# TEST_DCDC.net
KiCad netlist of a schematic drawn in EAGLE
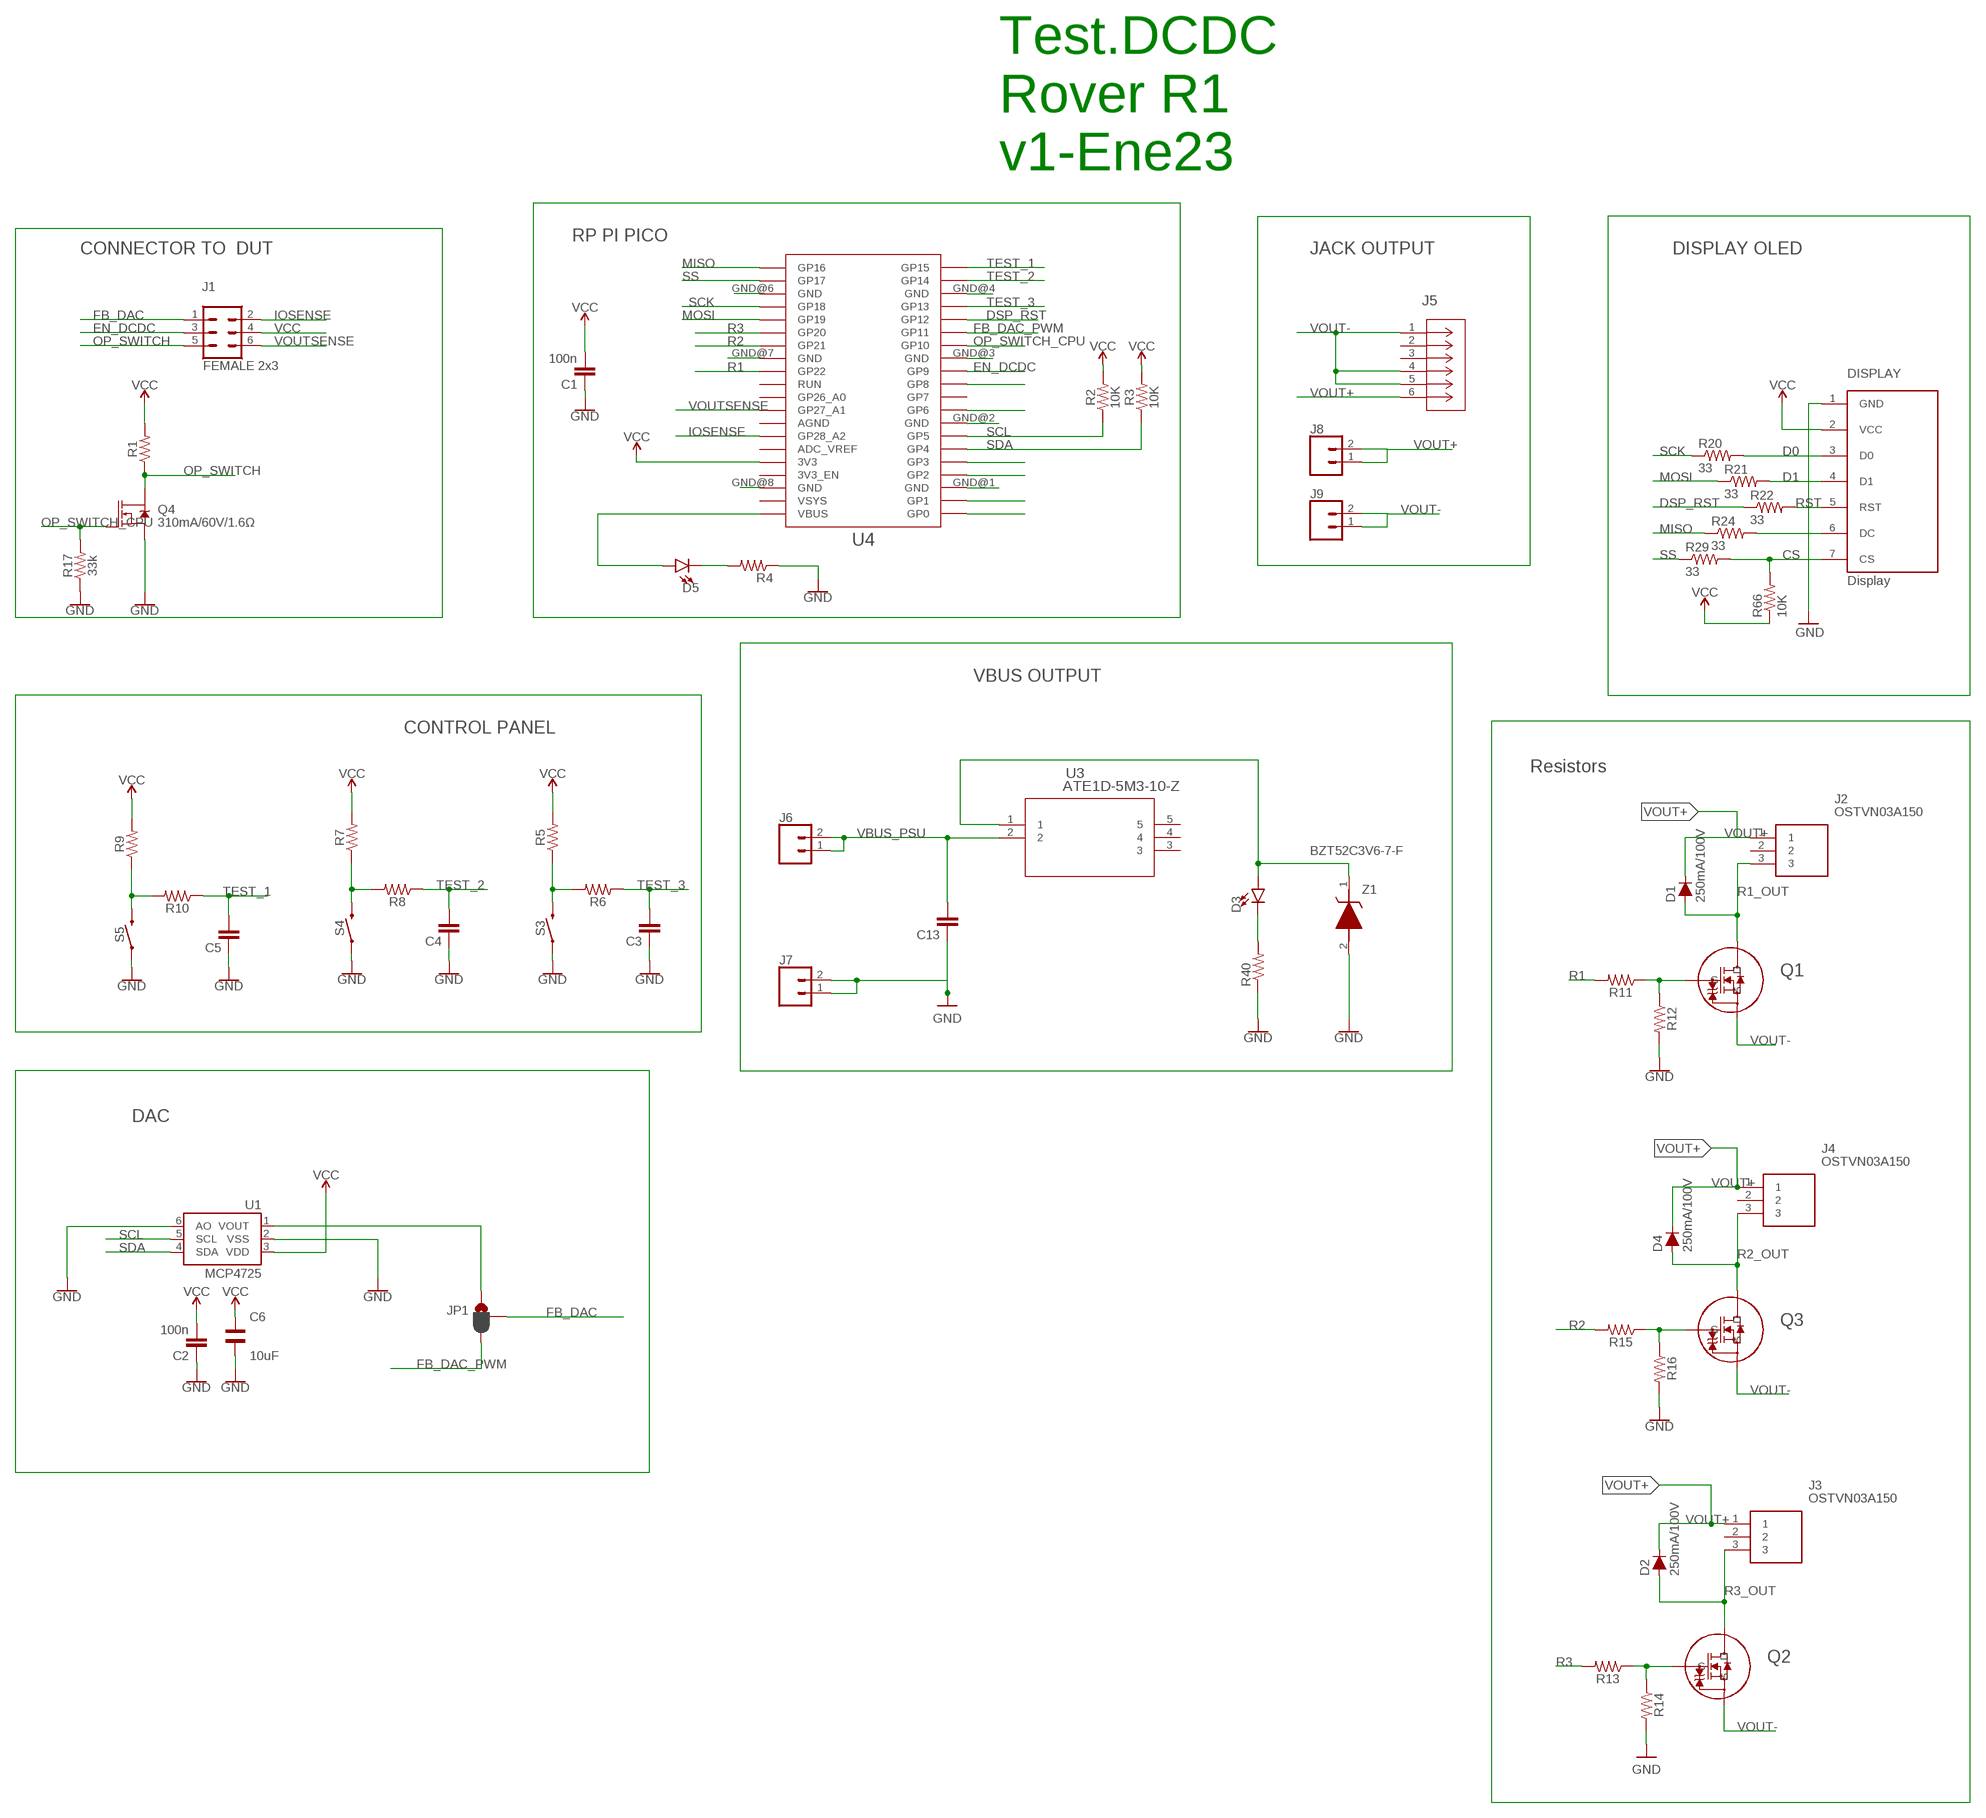
[diagram p0: schematic, sheet 1]

(export (version "E")
  (design (tool "Eeschema 10.0.6"))
  (components
    (comp (ref "C1")
      (value "100n")
      (footprint "eagle-import:C0805")
      (libsource (lib "eagle-import") (part "C-EUC0805"))
    )
    (comp (ref "C2")
      (value "100n")
      (footprint "eagle-import:C0805")
      (libsource (lib "eagle-import") (part "C-EUC0805"))
    )
    (comp (ref "C3")
      (value "C-EUC0805")
      (footprint "eagle-import:C0805")
      (libsource (lib "eagle-import") (part "C-EUC0805"))
    )
    (comp (ref "C4")
      (value "C-EUC0805")
      (footprint "eagle-import:C0805")
      (libsource (lib "eagle-import") (part "C-EUC0805"))
    )
    (comp (ref "C5")
      (value "C-EUC0805")
      (footprint "eagle-import:C0805")
      (libsource (lib "eagle-import") (part "C-EUC0805"))
    )
    (comp (ref "C6")
      (value "10uF")
      (footprint "eagle-import:WCAP-CSGP_1206")
      (libsource (lib "eagle-import") (part "WCAP-CSGP_1206_885012008001"))
    )
    (comp (ref "C13")
      (value "C-EUC0805")
      (footprint "eagle-import:C0805")
      (libsource (lib "eagle-import") (part "C-EUC0805"))
    )
    (comp (ref "D1")
      (value "250mA/100V")
      (footprint "eagle-import:SOD-323")
      (libsource (lib "eagle-import") (part "DIODE-BAS16J"))
    )
    (comp (ref "D2")
      (value "250mA/100V")
      (footprint "eagle-import:SOD-323")
      (libsource (lib "eagle-import") (part "DIODE-BAS16J"))
    )
    (comp (ref "D3")
      (value "LED3MM")
      (footprint "eagle-import:LED_3MM")
      (libsource (lib "eagle-import") (part "LED3MM"))
    )
    (comp (ref "D4")
      (value "250mA/100V")
      (footprint "eagle-import:SOD-323")
      (libsource (lib "eagle-import") (part "DIODE-BAS16J"))
    )
    (comp (ref "D5")
      (value "LED3MM")
      (footprint "eagle-import:LED_3MM")
      (libsource (lib "eagle-import") (part "LED3MM"))
    )
    (comp (ref "DISPLAY")
      (value "Display")
      (footprint "eagle-import:OLED_LCD")
      (libsource (lib "eagle-import") (part "OLED_LCD"))
    )
    (comp (ref "J1")
      (value "FEMALE 2x3")
      (footprint "eagle-import:2X3")
      (libsource (lib "eagle-import") (part "CONN_03X2FEMALE"))
    )
    (comp (ref "J2")
      (value "OSTVN03A150")
      (footprint "eagle-import:OSTVN03A150")
      (libsource (lib "eagle-import") (part "OSTVN03A150"))
    )
    (comp (ref "J3")
      (value "OSTVN03A150")
      (footprint "eagle-import:OSTVN03A150")
      (libsource (lib "eagle-import") (part "OSTVN03A150"))
    )
    (comp (ref "J4")
      (value "OSTVN03A150")
      (footprint "eagle-import:OSTVN03A150")
      (libsource (lib "eagle-import") (part "OSTVN03A150"))
    )
    (comp (ref "J5")
      (value "ACJS-MHDR")
      (footprint "eagle-import:CONN_MHDR_AMP")
      (fields (field (name "COPYRIGHT") "Copyright (C) 2018 Accelerated Designs. All rights reserved"))
      (libsource (lib "eagle-import") (part "ACJS-MHDR"))
    )
    (comp (ref "J6")
      (value "CONN_02")
      (footprint "eagle-import:1X02")
      (libsource (lib "eagle-import") (part "CONN_02"))
    )
    (comp (ref "J7")
      (value "CONN_02")
      (footprint "eagle-import:1X02")
      (libsource (lib "eagle-import") (part "CONN_02"))
    )
    (comp (ref "J8")
      (value "CONN_02")
      (footprint "eagle-import:1X02")
      (libsource (lib "eagle-import") (part "CONN_02"))
    )
    (comp (ref "J9")
      (value "CONN_02")
      (footprint "eagle-import:1X02")
      (libsource (lib "eagle-import") (part "CONN_02"))
    )
    (comp (ref "JP1")
      (value "JUMPER-SMT_3_1-NC_PASTE_SILK")
      (footprint "eagle-import:SMT-JUMPER_3_1-NC_PASTE_SILK")
      (libsource (lib "eagle-import") (part "JUMPER-SMT_3_1-NC_PASTE_SILK"))
    )
    (comp (ref "Q1")
      (value "PJA3416AE_R1_00001")
      (footprint "eagle-import:SOT23_PJA3416_PNJ")
      (fields (field (name "COPYRIGHT") "Copyright (C) 2022 Ultra Librarian. All rights reserved."))
      (libsource (lib "eagle-import") (part "PJA3416AE_R1_00001"))
    )
    (comp (ref "Q2")
      (value "PJA3416AE_R1_00001")
      (footprint "eagle-import:SOT23_PJA3416_PNJ")
      (fields (field (name "COPYRIGHT") "Copyright (C) 2022 Ultra Librarian. All rights reserved."))
      (libsource (lib "eagle-import") (part "PJA3416AE_R1_00001"))
    )
    (comp (ref "Q3")
      (value "PJA3416AE_R1_00001")
      (footprint "eagle-import:SOT23_PJA3416_PNJ")
      (fields (field (name "COPYRIGHT") "Copyright (C) 2022 Ultra Librarian. All rights reserved."))
      (libsource (lib "eagle-import") (part "PJA3416AE_R1_00001"))
    )
    (comp (ref "Q4")
      (value "310mA/60V/1.6Ω")
      (footprint "eagle-import:SOT323")
      (libsource (lib "eagle-import") (part "MOSFET-NCH-2N7002PW"))
    )
    (comp (ref "R1")
      (value "RESISTOR0805")
      (footprint "eagle-import:0805")
      (libsource (lib "eagle-import") (part "RESISTOR0805"))
    )
    (comp (ref "R2")
      (value "10K")
      (footprint "eagle-import:0805")
      (libsource (lib "eagle-import") (part "RESISTOR0805"))
    )
    (comp (ref "R3")
      (value "10K")
      (footprint "eagle-import:0805")
      (libsource (lib "eagle-import") (part "RESISTOR0805"))
    )
    (comp (ref "R4")
      (value "10K")
      (footprint "eagle-import:0805")
      (libsource (lib "eagle-import") (part "RESISTOR0805-RES"))
    )
    (comp (ref "R5")
      (value "RESISTOR0805")
      (footprint "eagle-import:0805")
      (libsource (lib "eagle-import") (part "RESISTOR0805"))
    )
    (comp (ref "R6")
      (value "RESISTOR0805")
      (footprint "eagle-import:0805")
      (libsource (lib "eagle-import") (part "RESISTOR0805"))
    )
    (comp (ref "R7")
      (value "RESISTOR0805")
      (footprint "eagle-import:0805")
      (libsource (lib "eagle-import") (part "RESISTOR0805"))
    )
    (comp (ref "R8")
      (value "RESISTOR0805")
      (footprint "eagle-import:0805")
      (libsource (lib "eagle-import") (part "RESISTOR0805"))
    )
    (comp (ref "R9")
      (value "RESISTOR0805")
      (footprint "eagle-import:0805")
      (libsource (lib "eagle-import") (part "RESISTOR0805"))
    )
    (comp (ref "R10")
      (value "RESISTOR0805")
      (footprint "eagle-import:0805")
      (libsource (lib "eagle-import") (part "RESISTOR0805"))
    )
    (comp (ref "R11")
      (value "RESISTOR0805")
      (footprint "eagle-import:0805")
      (libsource (lib "eagle-import") (part "RESISTOR0805"))
    )
    (comp (ref "R12")
      (value "RESISTOR0805")
      (footprint "eagle-import:0805")
      (libsource (lib "eagle-import") (part "RESISTOR0805"))
    )
    (comp (ref "R13")
      (value "RESISTOR0805")
      (footprint "eagle-import:0805")
      (libsource (lib "eagle-import") (part "RESISTOR0805"))
    )
    (comp (ref "R14")
      (value "RESISTOR0805")
      (footprint "eagle-import:0805")
      (libsource (lib "eagle-import") (part "RESISTOR0805"))
    )
    (comp (ref "R15")
      (value "RESISTOR0805")
      (footprint "eagle-import:0805")
      (libsource (lib "eagle-import") (part "RESISTOR0805"))
    )
    (comp (ref "R16")
      (value "RESISTOR0805")
      (footprint "eagle-import:0805")
      (libsource (lib "eagle-import") (part "RESISTOR0805"))
    )
    (comp (ref "R17")
      (value "33k")
      (footprint "eagle-import:0805")
      (libsource (lib "eagle-import") (part "RESISTOR0805"))
    )
    (comp (ref "R20")
      (value "33")
      (footprint "eagle-import:0805")
      (libsource (lib "eagle-import") (part "RESISTOR0805-RES"))
    )
    (comp (ref "R21")
      (value "33")
      (footprint "eagle-import:0805")
      (libsource (lib "eagle-import") (part "RESISTOR0805-RES"))
    )
    (comp (ref "R22")
      (value "33")
      (footprint "eagle-import:0805")
      (libsource (lib "eagle-import") (part "RESISTOR0805-RES"))
    )
    (comp (ref "R24")
      (value "33")
      (footprint "eagle-import:0805")
      (libsource (lib "eagle-import") (part "RESISTOR0805-RES"))
    )
    (comp (ref "R29")
      (value "33")
      (footprint "eagle-import:0805")
      (libsource (lib "eagle-import") (part "RESISTOR0805-RES"))
    )
    (comp (ref "R40")
      (value "10K")
      (footprint "eagle-import:0805")
      (libsource (lib "eagle-import") (part "RESISTOR0805-RES"))
    )
    (comp (ref "R66")
      (value "10K")
      (footprint "eagle-import:0805")
      (libsource (lib "eagle-import") (part "RESISTOR0805-RES"))
    )
    (comp (ref "S3")
      (value "MOMENTARY-SWITCH-SPST-SMD-5.2MM")
      (footprint "eagle-import:TACTILE_SWITCH_SMD_5.2MM")
      (libsource (lib "eagle-import") (part "MOMENTARY-SWITCH-SPST-SMD-5.2MM"))
    )
    (comp (ref "S4")
      (value "MOMENTARY-SWITCH-SPST-SMD-5.2MM")
      (footprint "eagle-import:TACTILE_SWITCH_SMD_5.2MM")
      (libsource (lib "eagle-import") (part "MOMENTARY-SWITCH-SPST-SMD-5.2MM"))
    )
    (comp (ref "S5")
      (value "MOMENTARY-SWITCH-SPST-SMD-5.2MM")
      (footprint "eagle-import:TACTILE_SWITCH_SMD_5.2MM")
      (libsource (lib "eagle-import") (part "MOMENTARY-SWITCH-SPST-SMD-5.2MM"))
    )
    (comp (ref "U1")
      (value "MCP4725")
      (footprint "eagle-import:SOT23-6")
      (libsource (lib "eagle-import") (part "MCP4725SOT-23"))
    )
    (comp (ref "U3")
      (value "ATE1D-5M3-10-Z")
      (footprint "eagle-import:SPDT05_ATE1D_9P5X8_NDC")
      (fields (field (name "COPYRIGHT") "Copyright (C) 2022 Ultra Librarian. All rights reserved."))
      (libsource (lib "eagle-import") (part "ATE1D-5M3-10-Z"))
    )
    (comp (ref "U4")
      (value "RPI_PICO_IG-TH")
      (footprint "eagle-import:RPI_PICO_TH")
      (libsource (lib "eagle-import") (part "RPI_PICO_IG-TH"))
    )
    (comp (ref "Z1")
      (value "BZT52C3V6-7-F")
      (footprint "eagle-import:SOD3716X135N")
      (fields (field (name "MOUSER_PART_NUMBER") "621-BZT52C3V6-F"))
      (libsource (lib "eagle-import") (part "BZT52C3V6-7-F"))
    )
  )
  (nets
    (net (code "1") (name "/CS") (class "Default")
      (node (ref "DISPLAY") (pin "7") (pinfunction "CS_7") (pintype "bidirectional"))
      (node (ref "R29") (pin "2") (pinfunction "2_2") (pintype "passive"))
      (node (ref "R66") (pin "2") (pinfunction "2_2") (pintype "passive"))
    )
    (net (code "2") (name "/D0") (class "Default")
      (node (ref "DISPLAY") (pin "3") (pinfunction "D0_3") (pintype "bidirectional"))
      (node (ref "R20") (pin "2") (pinfunction "2_2") (pintype "passive"))
    )
    (net (code "3") (name "/D1") (class "Default")
      (node (ref "DISPLAY") (pin "4") (pinfunction "D1_4") (pintype "bidirectional"))
      (node (ref "R21") (pin "2") (pinfunction "2_2") (pintype "passive"))
    )
    (net (code "4") (name "/DSP_RST") (class "Default")
      (node (ref "R22") (pin "1") (pinfunction "1_1") (pintype "passive"))
      (node (ref "U4") (pin "GP12") (pinfunction "GP12_GP12") (pintype "bidirectional"))
    )
    (net (code "5") (name "/EN_DCDC") (class "Default")
      (node (ref "J1") (pin "3") (pinfunction "3_3") (pintype "bidirectional"))
      (node (ref "U4") (pin "GP9") (pinfunction "GP9_GP9") (pintype "bidirectional"))
    )
    (net (code "6") (name "/FB_DAC") (class "Default")
      (node (ref "J1") (pin "1") (pinfunction "1_1") (pintype "bidirectional"))
      (node (ref "JP1") (pin "2") (pinfunction "2_2") (pintype "passive"))
    )
    (net (code "7") (name "/FB_DAC_PWM") (class "Default")
      (node (ref "JP1") (pin "3") (pinfunction "3_3") (pintype "passive"))
      (node (ref "U4") (pin "GP11") (pinfunction "GP11_GP11") (pintype "bidirectional"))
    )
    (net (code "8") (name "/IOSENSE") (class "Default")
      (node (ref "J1") (pin "2") (pinfunction "2_2") (pintype "bidirectional"))
      (node (ref "U4") (pin "GP28_A2") (pinfunction "GP28_A2_GP28_A2") (pintype "bidirectional"))
    )
    (net (code "9") (name "/MISO") (class "Default")
      (node (ref "R24") (pin "1") (pinfunction "1_1") (pintype "passive"))
      (node (ref "U4") (pin "GP16") (pinfunction "GP16_GP16") (pintype "bidirectional"))
    )
    (net (code "10") (name "/MOSI") (class "Default")
      (node (ref "R21") (pin "1") (pinfunction "1_1") (pintype "passive"))
      (node (ref "U4") (pin "GP19") (pinfunction "GP19_GP19") (pintype "bidirectional"))
    )
    (net (code "11") (name "/OP_SWITCH") (class "Default")
      (node (ref "J1") (pin "5") (pinfunction "5_5") (pintype "bidirectional"))
      (node (ref "Q4") (pin "3") (pinfunction "D_3") (pintype "bidirectional"))
      (node (ref "R1") (pin "1") (pinfunction "1_1") (pintype "passive"))
    )
    (net (code "12") (name "/OP_SWITCH_CPU") (class "Default")
      (node (ref "Q4") (pin "1") (pinfunction "G_1") (pintype "bidirectional"))
      (node (ref "R17") (pin "2") (pinfunction "2_2") (pintype "passive"))
      (node (ref "U4") (pin "GP10") (pinfunction "GP10_GP10") (pintype "bidirectional"))
    )
    (net (code "13") (name "/R1") (class "Default")
      (node (ref "R11") (pin "2") (pinfunction "2_2") (pintype "passive"))
      (node (ref "U4") (pin "GP22") (pinfunction "GP22_GP22") (pintype "bidirectional"))
    )
    (net (code "14") (name "/R1_OUT") (class "Default")
      (node (ref "D1") (pin "A") (pinfunction "A_A") (pintype "passive"))
      (node (ref "J2") (pin "3") (pinfunction "3_3") (pintype "bidirectional"))
      (node (ref "Q1") (pin "3") (pinfunction "D_3") (pintype "passive"))
    )
    (net (code "15") (name "/R2") (class "Default")
      (node (ref "R15") (pin "2") (pinfunction "2_2") (pintype "passive"))
      (node (ref "U4") (pin "GP21") (pinfunction "GP21_GP21") (pintype "bidirectional"))
    )
    (net (code "16") (name "/R2_OUT") (class "Default")
      (node (ref "D4") (pin "A") (pinfunction "A_A") (pintype "passive"))
      (node (ref "J4") (pin "3") (pinfunction "3_3") (pintype "bidirectional"))
      (node (ref "Q3") (pin "3") (pinfunction "D_3") (pintype "passive"))
    )
    (net (code "17") (name "/R3") (class "Default")
      (node (ref "R13") (pin "2") (pinfunction "2_2") (pintype "passive"))
      (node (ref "U4") (pin "GP20") (pinfunction "GP20_GP20") (pintype "bidirectional"))
    )
    (net (code "18") (name "/R3_OUT") (class "Default")
      (node (ref "D2") (pin "A") (pinfunction "A_A") (pintype "passive"))
      (node (ref "J3") (pin "3") (pinfunction "3_3") (pintype "bidirectional"))
      (node (ref "Q2") (pin "3") (pinfunction "D_3") (pintype "passive"))
    )
    (net (code "19") (name "/RST") (class "Default")
      (node (ref "DISPLAY") (pin "5") (pinfunction "RST_5") (pintype "bidirectional"))
      (node (ref "R22") (pin "2") (pinfunction "2_2") (pintype "passive"))
    )
    (net (code "20") (name "/SCK") (class "Default")
      (node (ref "R20") (pin "1") (pinfunction "1_1") (pintype "passive"))
      (node (ref "U4") (pin "GP18") (pinfunction "GP18_GP18") (pintype "bidirectional"))
    )
    (net (code "21") (name "/SCL") (class "Default")
      (node (ref "R2") (pin "1") (pinfunction "1_1") (pintype "passive"))
      (node (ref "U1") (pin "5") (pinfunction "SCL_5") (pintype "bidirectional"))
      (node (ref "U4") (pin "GP5") (pinfunction "GP5_GP5") (pintype "bidirectional"))
    )
    (net (code "22") (name "/SDA") (class "Default")
      (node (ref "R3") (pin "1") (pinfunction "1_1") (pintype "passive"))
      (node (ref "U1") (pin "4") (pinfunction "SDA_4") (pintype "bidirectional"))
      (node (ref "U4") (pin "GP4") (pinfunction "GP4_GP4") (pintype "bidirectional"))
    )
    (net (code "23") (name "/SS") (class "Default")
      (node (ref "R29") (pin "1") (pinfunction "1_1") (pintype "passive"))
      (node (ref "U4") (pin "GP17") (pinfunction "GP17_GP17") (pintype "bidirectional"))
    )
    (net (code "24") (name "/TEST_1") (class "Default")
      (node (ref "C5") (pin "2") (pinfunction "2_2") (pintype "passive"))
      (node (ref "R10") (pin "1") (pinfunction "1_1") (pintype "passive"))
      (node (ref "U4") (pin "GP15") (pinfunction "GP15_GP15") (pintype "bidirectional"))
    )
    (net (code "25") (name "/TEST_2") (class "Default")
      (node (ref "C4") (pin "2") (pinfunction "2_2") (pintype "passive"))
      (node (ref "R8") (pin "1") (pinfunction "1_1") (pintype "passive"))
      (node (ref "U4") (pin "GP14") (pinfunction "GP14_GP14") (pintype "bidirectional"))
    )
    (net (code "26") (name "/TEST_3") (class "Default")
      (node (ref "C3") (pin "2") (pinfunction "2_2") (pintype "passive"))
      (node (ref "R6") (pin "1") (pinfunction "1_1") (pintype "passive"))
      (node (ref "U4") (pin "GP13") (pinfunction "GP13_GP13") (pintype "bidirectional"))
    )
    (net (code "27") (name "/VBUS_PSU") (class "Default")
      (node (ref "C13") (pin "2") (pinfunction "2_2") (pintype "passive"))
      (node (ref "J6") (pin "1") (pinfunction "1_1") (pintype "passive"))
      (node (ref "J6") (pin "2") (pinfunction "2_2") (pintype "passive"))
      (node (ref "U3") (pin "2") (pinfunction "2_2") (pintype "passive"))
    )
    (net (code "28") (name "/VOUT-") (class "Default")
      (node (ref "J5") (pin "1") (pinfunction "1_1") (pintype "passive"))
      (node (ref "J5") (pin "4") (pinfunction "4_4") (pintype "passive"))
      (node (ref "J5") (pin "5") (pinfunction "5_5") (pintype "passive"))
      (node (ref "J9") (pin "1") (pinfunction "1_1") (pintype "passive"))
      (node (ref "J9") (pin "2") (pinfunction "2_2") (pintype "passive"))
      (node (ref "Q1") (pin "2") (pinfunction "S_2") (pintype "passive"))
      (node (ref "Q2") (pin "2") (pinfunction "S_2") (pintype "passive"))
      (node (ref "Q3") (pin "2") (pinfunction "S_2") (pintype "passive"))
    )
    (net (code "29") (name "/VOUTSENSE") (class "Default")
      (node (ref "J1") (pin "6") (pinfunction "6_6") (pintype "bidirectional"))
      (node (ref "U4") (pin "GP27_A1") (pinfunction "GP27_A1_GP27_A1") (pintype "bidirectional"))
    )
    (net (code "30") (name "GND") (class "Default")
      (node (ref "C1") (pin "1") (pinfunction "1_1") (pintype "passive"))
      (node (ref "C13") (pin "1") (pinfunction "1_1") (pintype "passive"))
      (node (ref "C2") (pin "1") (pinfunction "1_1") (pintype "passive"))
      (node (ref "C3") (pin "1") (pinfunction "1_1") (pintype "passive"))
      (node (ref "C4") (pin "1") (pinfunction "1_1") (pintype "passive"))
      (node (ref "C5") (pin "1") (pinfunction "1_1") (pintype "passive"))
      (node (ref "C6") (pin "1") (pinfunction "1_1") (pintype "passive"))
      (node (ref "DISPLAY") (pin "1") (pinfunction "GND_1") (pintype "bidirectional"))
      (node (ref "J7") (pin "1") (pinfunction "1_1") (pintype "passive"))
      (node (ref "J7") (pin "2") (pinfunction "2_2") (pintype "passive"))
      (node (ref "Q4") (pin "2") (pinfunction "S_2") (pintype "bidirectional"))
      (node (ref "R12") (pin "2") (pinfunction "2_2") (pintype "passive"))
      (node (ref "R14") (pin "2") (pinfunction "2_2") (pintype "passive"))
      (node (ref "R16") (pin "2") (pinfunction "2_2") (pintype "passive"))
      (node (ref "R17") (pin "1") (pinfunction "1_1") (pintype "passive"))
      (node (ref "R4") (pin "1") (pinfunction "1_1") (pintype "passive"))
      (node (ref "R40") (pin "1") (pinfunction "1_1") (pintype "passive"))
      (node (ref "S3") (pin "1") (pinfunction "1_1") (pintype "passive"))
      (node (ref "S4") (pin "1") (pinfunction "1_1") (pintype "passive"))
      (node (ref "S5") (pin "1") (pinfunction "1_1") (pintype "passive"))
      (node (ref "U1") (pin "2") (pinfunction "VSS_2") (pintype "bidirectional"))
      (node (ref "U1") (pin "6") (pinfunction "AO_6") (pintype "bidirectional"))
      (node (ref "U4") (pin "GND@1") (pinfunction "GND_GND@1") (pintype "bidirectional"))
      (node (ref "U4") (pin "GND@2") (pinfunction "GND_GND@2") (pintype "bidirectional"))
      (node (ref "U4") (pin "GND@3") (pinfunction "GND_GND@3") (pintype "bidirectional"))
      (node (ref "U4") (pin "GND@4") (pinfunction "GND_GND@4") (pintype "bidirectional"))
      (node (ref "U4") (pin "GND@6") (pinfunction "GND_GND@6") (pintype "bidirectional"))
      (node (ref "U4") (pin "GND@7") (pinfunction "GND_GND@7") (pintype "bidirectional"))
      (node (ref "U4") (pin "GND@8") (pinfunction "GND_GND@8") (pintype "bidirectional"))
      (node (ref "Z1") (pin "2") (pinfunction "A_2") (pintype "bidirectional"))
    )
    (net (code "31") (name "Net-(D3-C)") (class "Default")
      (node (ref "D3") (pin "K") (pinfunction "C_K") (pintype "passive"))
      (node (ref "R40") (pin "2") (pinfunction "2_2") (pintype "passive"))
    )
    (net (code "32") (name "Net-(D5-C)") (class "Default")
      (node (ref "D5") (pin "K") (pinfunction "C_K") (pintype "passive"))
      (node (ref "R4") (pin "2") (pinfunction "2_2") (pintype "passive"))
    )
    (net (code "33") (name "Net-(D5-PadA)") (class "Default")
      (node (ref "D5") (pin "A") (pinfunction "A_A") (pintype "passive"))
      (node (ref "U4") (pin "VBUS") (pinfunction "VBUS_VBUS") (pintype "bidirectional"))
    )
    (net (code "34") (name "Net-(DISPLAY-DC)") (class "Default")
      (node (ref "DISPLAY") (pin "6") (pinfunction "DC_6") (pintype "bidirectional"))
      (node (ref "R24") (pin "2") (pinfunction "2_2") (pintype "passive"))
    )
    (net (code "35") (name "Net-(Q1-G)") (class "Default")
      (node (ref "Q1") (pin "1") (pinfunction "G_1") (pintype "passive"))
      (node (ref "R11") (pin "1") (pinfunction "1_1") (pintype "passive"))
      (node (ref "R12") (pin "1") (pinfunction "1_1") (pintype "passive"))
    )
    (net (code "36") (name "Net-(Q2-G)") (class "Default")
      (node (ref "Q2") (pin "1") (pinfunction "G_1") (pintype "passive"))
      (node (ref "R13") (pin "1") (pinfunction "1_1") (pintype "passive"))
      (node (ref "R14") (pin "1") (pinfunction "1_1") (pintype "passive"))
    )
    (net (code "37") (name "Net-(Q3-G)") (class "Default")
      (node (ref "Q3") (pin "1") (pinfunction "G_1") (pintype "passive"))
      (node (ref "R15") (pin "1") (pinfunction "1_1") (pintype "passive"))
      (node (ref "R16") (pin "1") (pinfunction "1_1") (pintype "passive"))
    )
    (net (code "38") (name "Net-(S3-2)") (class "Default")
      (node (ref "R5") (pin "1") (pinfunction "1_1") (pintype "passive"))
      (node (ref "R6") (pin "2") (pinfunction "2_2") (pintype "passive"))
      (node (ref "S3") (pin "3") (pinfunction "2_3") (pintype "passive"))
    )
    (net (code "39") (name "Net-(S4-2)") (class "Default")
      (node (ref "R7") (pin "1") (pinfunction "1_1") (pintype "passive"))
      (node (ref "R8") (pin "2") (pinfunction "2_2") (pintype "passive"))
      (node (ref "S4") (pin "3") (pinfunction "2_3") (pintype "passive"))
    )
    (net (code "40") (name "Net-(S5-2)") (class "Default")
      (node (ref "R10") (pin "2") (pinfunction "2_2") (pintype "passive"))
      (node (ref "R9") (pin "1") (pinfunction "1_1") (pintype "passive"))
      (node (ref "S5") (pin "3") (pinfunction "2_3") (pintype "passive"))
    )
    (net (code "41") (name "Net-(U1-VOUT)") (class "Default")
      (node (ref "JP1") (pin "1") (pinfunction "1_1") (pintype "passive"))
      (node (ref "U1") (pin "1") (pinfunction "VOUT_1") (pintype "bidirectional"))
    )
    (net (code "42") (name "Net-(Z1-K)") (class "Default")
      (node (ref "D3") (pin "A") (pinfunction "A_A") (pintype "passive"))
      (node (ref "U3") (pin "1") (pinfunction "1_1") (pintype "passive"))
      (node (ref "Z1") (pin "1") (pinfunction "K_1") (pintype "bidirectional"))
    )
    (net (code "43") (name "VCC") (class "Default")
      (node (ref "C1") (pin "2") (pinfunction "2_2") (pintype "passive"))
      (node (ref "C2") (pin "2") (pinfunction "2_2") (pintype "passive"))
      (node (ref "C6") (pin "2") (pinfunction "2_2") (pintype "passive"))
      (node (ref "DISPLAY") (pin "2") (pinfunction "VCC_2") (pintype "bidirectional"))
      (node (ref "J1") (pin "4") (pinfunction "4_4") (pintype "bidirectional"))
      (node (ref "R1") (pin "2") (pinfunction "2_2") (pintype "passive"))
      (node (ref "R2") (pin "2") (pinfunction "2_2") (pintype "passive"))
      (node (ref "R3") (pin "2") (pinfunction "2_2") (pintype "passive"))
      (node (ref "R5") (pin "2") (pinfunction "2_2") (pintype "passive"))
      (node (ref "R66") (pin "1") (pinfunction "1_1") (pintype "passive"))
      (node (ref "R7") (pin "2") (pinfunction "2_2") (pintype "passive"))
      (node (ref "R9") (pin "2") (pinfunction "2_2") (pintype "passive"))
      (node (ref "U1") (pin "3") (pinfunction "VDD_3") (pintype "bidirectional"))
      (node (ref "U4") (pin "3V3") (pinfunction "3V3_3V3") (pintype "bidirectional"))
    )
    (net (code "44") (name "VOUT+") (class "Default")
      (node (ref "D1") (pin "C") (pinfunction "C_C") (pintype "passive"))
      (node (ref "D2") (pin "C") (pinfunction "C_C") (pintype "passive"))
      (node (ref "D4") (pin "C") (pinfunction "C_C") (pintype "passive"))
      (node (ref "J2") (pin "1") (pinfunction "1_1") (pintype "bidirectional"))
      (node (ref "J3") (pin "1") (pinfunction "1_1") (pintype "bidirectional"))
      (node (ref "J4") (pin "1") (pinfunction "1_1") (pintype "bidirectional"))
      (node (ref "J5") (pin "6") (pinfunction "6_6") (pintype "passive"))
      (node (ref "J8") (pin "1") (pinfunction "1_1") (pintype "passive"))
      (node (ref "J8") (pin "2") (pinfunction "2_2") (pintype "passive"))
    )
    (net (code "45") (name "unconnected-(J2-Pad2)") (class "Default")
      (node (ref "J2") (pin "2") (pinfunction "2_2") (pintype "bidirectional"))
    )
    (net (code "46") (name "unconnected-(J3-Pad2)") (class "Default")
      (node (ref "J3") (pin "2") (pinfunction "2_2") (pintype "bidirectional"))
    )
    (net (code "47") (name "unconnected-(J4-Pad2)") (class "Default")
      (node (ref "J4") (pin "2") (pinfunction "2_2") (pintype "bidirectional"))
    )
    (net (code "48") (name "unconnected-(J5-Pad2)") (class "Default")
      (node (ref "J5") (pin "2") (pinfunction "2_2") (pintype "passive"))
    )
    (net (code "49") (name "unconnected-(J5-Pad3)") (class "Default")
      (node (ref "J5") (pin "3") (pinfunction "3_3") (pintype "passive"))
    )
    (net (code "50") (name "unconnected-(U3-Pad3)") (class "Default")
      (node (ref "U3") (pin "3") (pinfunction "3_3") (pintype "passive"))
    )
    (net (code "51") (name "unconnected-(U3-Pad4)") (class "Default")
      (node (ref "U3") (pin "4") (pinfunction "4_4") (pintype "passive"))
    )
    (net (code "52") (name "unconnected-(U3-Pad5)") (class "Default")
      (node (ref "U3") (pin "5") (pinfunction "5_5") (pintype "passive"))
    )
    (net (code "53") (name "unconnected-(U4-Pad3V3_EN)") (class "Default")
      (node (ref "U4") (pin "3V3_EN") (pinfunction "3V3_EN_3V3_EN") (pintype "bidirectional"))
    )
    (net (code "54") (name "unconnected-(U4-PadADC_VREF)") (class "Default")
      (node (ref "U4") (pin "ADC_VREF") (pinfunction "ADC_VREF_ADC_VREF") (pintype "bidirectional"))
    )
    (net (code "55") (name "unconnected-(U4-PadAGND)") (class "Default")
      (node (ref "U4") (pin "AGND") (pinfunction "AGND_AGND") (pintype "bidirectional"))
    )
    (net (code "56") (name "unconnected-(U4-PadGP0)") (class "Default")
      (node (ref "U4") (pin "GP0") (pinfunction "GP0_GP0") (pintype "bidirectional"))
    )
    (net (code "57") (name "unconnected-(U4-PadGP1)") (class "Default")
      (node (ref "U4") (pin "GP1") (pinfunction "GP1_GP1") (pintype "bidirectional"))
    )
    (net (code "58") (name "unconnected-(U4-PadGP2)") (class "Default")
      (node (ref "U4") (pin "GP2") (pinfunction "GP2_GP2") (pintype "bidirectional"))
    )
    (net (code "59") (name "unconnected-(U4-PadGP3)") (class "Default")
      (node (ref "U4") (pin "GP3") (pinfunction "GP3_GP3") (pintype "bidirectional"))
    )
    (net (code "60") (name "unconnected-(U4-PadGP6)") (class "Default")
      (node (ref "U4") (pin "GP6") (pinfunction "GP6_GP6") (pintype "bidirectional"))
    )
    (net (code "61") (name "unconnected-(U4-PadGP7)") (class "Default")
      (node (ref "U4") (pin "GP7") (pinfunction "GP7_GP7") (pintype "bidirectional"))
    )
    (net (code "62") (name "unconnected-(U4-PadGP8)") (class "Default")
      (node (ref "U4") (pin "GP8") (pinfunction "GP8_GP8") (pintype "bidirectional"))
    )
    (net (code "63") (name "unconnected-(U4-PadGP26_A0)") (class "Default")
      (node (ref "U4") (pin "GP26_A0") (pinfunction "GP26_A0_GP26_A0") (pintype "bidirectional"))
    )
    (net (code "64") (name "unconnected-(U4-PadRUN)") (class "Default")
      (node (ref "U4") (pin "RUN") (pinfunction "RUN_RUN") (pintype "bidirectional"))
    )
    (net (code "65") (name "unconnected-(U4-PadVSYS)") (class "Default")
      (node (ref "U4") (pin "VSYS") (pinfunction "VSYS_VSYS") (pintype "bidirectional"))
    )
  )
)
